# milestone1.net
KiCad netlist of a schematic drawn in Altium Designer
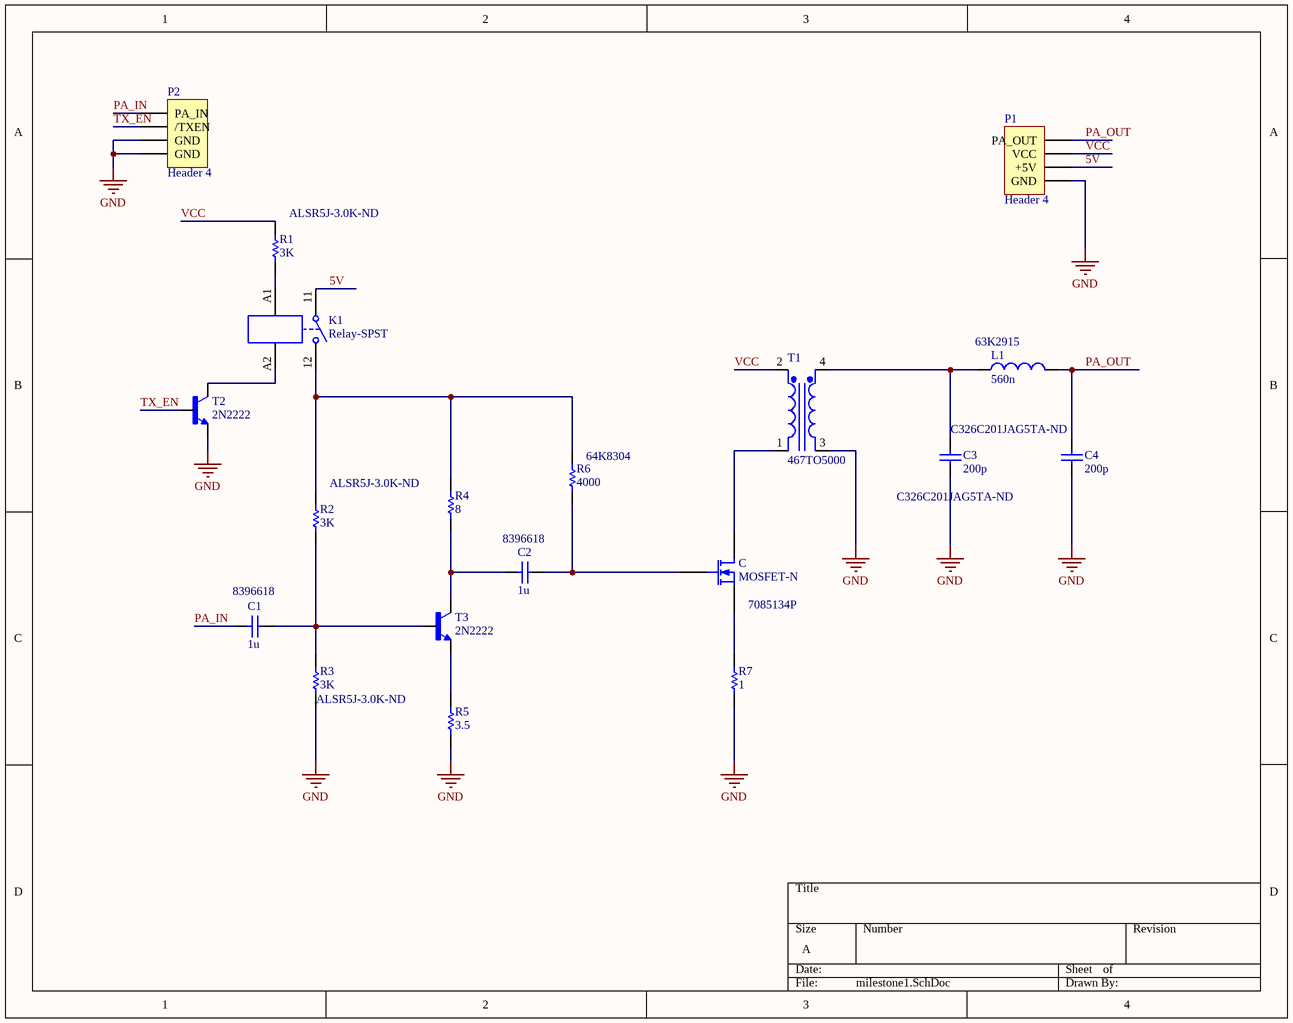
[diagram p0: milestone1.SchDoc]

(export (version "E")
  (design (tool "Eeschema 10.0.6"))
  (components
    (comp (ref "C")
      (value "MOSFET-N")
      (footprint "TO254P1067X483X3124-3P")
      (description "IRF510PBF N-channel MOSFET Transistor; 5.6 A; 100 V; 3-Pin TO-220AB")
      (fields
        (field (name "SUPPLIER PART NUMBER 1") "7085134P")
        (field (name "MANUFACTURER") "Vishay")
        (field (name "MANUFACTURER PART NUMBER") "IRF510PBF")
        (field (name "PUBLISHER") "Altium Limited")
      )
      (libsource (lib "Miscellaneous Devices") (part "MOSFET-N"))
    )
    (comp (ref "C1")
      (value "1u")
      (footprint "RAD-0.1")
      (description "Alum. Electrolytic Cap 1µF 50V 5mm Radial WCAP-ATG5 Series Lifetime 2000h +105°C")
      (fields
        (field (name "MANUFACTURER") "CDE Illinois Capacitor")
        (field (name "MANUFACTURER PART NUMBER") "109CKS016M")
        (field (name "SUPPLIER PART NUMBER 2") "8396618")
      )
      (libsource (lib "Simulation Generic Components") (part "Capacitor"))
    )
    (comp (ref "C2")
      (value "1u")
      (footprint "RAD-0.1")
      (description "Alum. Electrolytic Cap 1µF 50V 5mm Radial WCAP-ATG5 Series Lifetime 2000h +105°C")
      (fields
        (field (name "SUPPLIER PART NUMBER 1") "8396618")
        (field (name "MANUFACTURER") "Wurth Electronics")
        (field (name "MANUFACTURER PART NUMBER") "860020672005")
      )
      (libsource (lib "Simulation Generic Components") (part "Capacitor"))
    )
    (comp (ref "C3")
      (value "200p")
      (footprint "rad-0.1")
      (description "Capacitor Multi-layer Ceramic 200pF 5% 250V 2-Pin Through Hole Bulk")
      (fields
        (field (name "SUPPLIER PART NUMBER 1") "C326C201JAG5TA-ND")
        (field (name "MANUFACTURER") "KEMET")
        (field (name "MANUFACTURER PART NUMBER") "C326C201JAG5TA")
      )
      (libsource (lib "Simulation Generic Components") (part "Capacitor"))
    )
    (comp (ref "C4")
      (value "200p")
      (footprint "rad-0.1")
      (description "Capacitor Multi-layer Ceramic 200pF 5% 250V 2-Pin Through Hole Bulk")
      (fields
        (field (name "SUPPLIER PART NUMBER 1") "C326C201JAG5TA-ND")
        (field (name "MANUFACTURER") "KEMET")
        (field (name "MANUFACTURER PART NUMBER") "C326C201JAG5TA")
      )
      (libsource (lib "Simulation Generic Components") (part "Capacitor"))
    )
    (comp (ref "K1")
      (value "Relay-SPST")
      (footprint "Relay:PCBComponent_1")
      (description "Single-Pole Single-Throw Relay")
      (fields (field (name "PUBLISHER") "Altium Limited"))
      (libsource (lib "Miscellaneous Devices") (part "Relay-SPST"))
    )
    (comp (ref "L1")
      (value "560n")
      (footprint "AXIAL-0.4")
      (description "Inductor")
      (fields (field (name "SUPPLIER PART NUMBER 2") "63K2915"))
      (libsource (lib "Simulation Generic Components") (part "Inductor"))
    )
    (comp (ref "P1")
      (value "Header 4")
      (footprint "HDR1X4")
      (description "Header, 4-Pin")
      (fields (field (name "PUBLISHER") "Altium Limited"))
      (libsource (lib "") (part "Header 4_1"))
    )
    (comp (ref "P2")
      (value "Header 4")
      (footprint "HDR1X4")
      (description "Header, 4-Pin")
      (fields (field (name "PUBLISHER") "Altium Limited"))
      (libsource (lib "Miscellaneous Connectors") (part "Header 4"))
    )
    (comp (ref "R1")
      (value "3K")
      (footprint "AXIAL-0.4")
      (description "Res Wirewound 3K Ohm 5% 5W ±30ppm/°C Ceramic Hi Temp Sil AXL Thru-Hole Bulk")
      (fields
        (field (name "MANUFACTURER") "Vishay BCcomponents")
        (field (name "MANUFACTURER PART NUMBER") "MBA02040C3001FC100")
        (field (name "SUPPLIER PART NUMBER 2") "ALSR5J-3.0K-ND")
      )
      (libsource (lib "Simulation Generic Components") (part "Resistor"))
    )
    (comp (ref "R2")
      (value "3K")
      (footprint "AXIAL-0.4")
      (description "Res Wirewound 3K Ohm 5% 5W ±30ppm/°C Ceramic Hi Temp Sil AXL Thru-Hole Bulk")
      (fields
        (field (name "MANUFACTURER") "Vishay BCcomponents")
        (field (name "MANUFACTURER PART NUMBER") "MBA02040C3001FC100")
        (field (name "SUPPLIER PART NUMBER 2") "ALSR5J-3.0K-ND")
      )
      (libsource (lib "Simulation Generic Components") (part "Resistor"))
    )
    (comp (ref "R3")
      (value "3K")
      (footprint "AXIAL-0.4")
      (description "Res Wirewound 3K Ohm 5% 5W ±30ppm/°C Ceramic Hi Temp Sil AXL Thru-Hole Bulk")
      (fields
        (field (name "MANUFACTURER") "Vishay BCcomponents")
        (field (name "MANUFACTURER PART NUMBER") "MBA02040C3001FC100")
        (field (name "SUPPLIER PART NUMBER 3") "ALSR5J-3.0K-ND")
      )
      (libsource (lib "Simulation Generic Components") (part "Resistor"))
    )
    (comp (ref "R4")
      (value "8")
      (footprint "rad-0.1")
      (description "Resistor; Wirewound; Res 33 Ohms; Pwr-Rtg 5 W; Tol 1%; Axial; Silicone-Ceramic")
      (fields
        (field (name "MANUFACTURER") "Piher")
        (field (name "MANUFACTURER PART NUMBER") "N6S25T0C-504-3030")
      )
      (libsource (lib "Simulation Generic Components") (part "Resistor"))
    )
    (comp (ref "R5")
      (value "3.5")
      (footprint "rad-0.1")
      (description "Res Metal Film 1.5 Ohm 5% 3W ±300ppm/°C Conformal AXL Thru-Hole")
      (fields
        (field (name "MANUFACTURER") "Vishay Dale")
        (field (name "MANUFACTURER PART NUMBER") "RN70C2700BB14")
      )
      (libsource (lib "Simulation Generic Components") (part "Resistor"))
    )
    (comp (ref "R6")
      (value "4000")
      (footprint "AXIAL-0.4")
      (description "Resistor, Wirewound, Res 4 Kilohms, Pwr-Rtg 5 W, Tol 5%, Axial, Vitreous Enamel")
      (fields
        (field (name "MANUFACTURER") "Piher")
        (field (name "MANUFACTURER PART NUMBER") "N6S25T0C-504-3030")
        (field (name "SUPPLIER PART NUMBER 3") "64K8304")
      )
      (libsource (lib "Simulation Generic Components") (part "Resistor"))
    )
    (comp (ref "R7")
      (value "1")
      (footprint "AXIAL-0.4")
      (description "Res Wirewound 8K Ohm 5% 5W ±30ppm/°C Ceramic Hi Temp Sil AXL Thru-Hole Bulk")
      (fields
        (field (name "MANUFACTURER") "Vishay Dale")
        (field (name "MANUFACTURER PART NUMBER") "RN55C8001BB14")
      )
      (libsource (lib "Simulation Generic Components") (part "Resistor"))
    )
    (comp (ref "T1")
      (value "467TO5000")
      (footprint "TRANS")
      (description "Transformer (Ideal)")
      (fields (field (name "PUBLISHER") "Altium Limited"))
      (libsource (lib "Miscellaneous Devices") (part "Trans Ideal"))
    )
    (comp (ref "T2")
      (value "2N2222")
      (footprint "TO92-EBC-OVAL")
      (description "Bipolar (BJT) Transistor NPN 40V 800mA 300MHz 500mW Through Hole TO-18")
      (fields (field (name "MF") "ON Semiconductor"))
      (libsource (lib "2N2222 (2)") (part "2N2222"))
    )
    (comp (ref "T3")
      (value "2N2222")
      (footprint "TO92-EBC-OVAL")
      (description "Bipolar (BJT) Transistor NPN 40V 800mA 300MHz 500mW Through Hole TO-18")
      (fields (field (name "MF") "ON Semiconductor"))
      (libsource (lib "2N2222 (2)") (part "2N2222"))
    )
  )
  (nets
    (net (code "1") (name "/5V") (class "Default")
      (node (ref "K1") (pin "11") (pinfunction "SW1_11") (pintype "passive"))
      (node (ref "P1") (pin "2") (pinfunction "+5V_2") (pintype "passive"))
    )
    (net (code "2") (name "/PA_IN") (class "Default")
      (node (ref "C1") (pin "1") (pinfunction "1_1") (pintype "passive"))
      (node (ref "P2") (pin "1") (pinfunction "PA_IN_1") (pintype "passive"))
    )
    (net (code "3") (name "/PA_OUT") (class "Default")
      (node (ref "C4") (pin "2") (pinfunction "2_2") (pintype "passive"))
      (node (ref "L1") (pin "2") (pinfunction "2_2") (pintype "passive"))
      (node (ref "P1") (pin "4") (pinfunction "PA_OUT_4") (pintype "passive"))
    )
    (net (code "4") (name "/TX_EN") (class "Default")
      (node (ref "P2") (pin "2") (pinfunction "/TXEN_2") (pintype "passive"))
      (node (ref "T2") (pin "B") (pinfunction "B_B") (pintype "passive"))
    )
    (net (code "5") (name "/VCC") (class "Default")
      (node (ref "P1") (pin "3") (pinfunction "VCC_3") (pintype "passive"))
      (node (ref "R1") (pin "2") (pinfunction "2_2") (pintype "passive"))
      (node (ref "T1") (pin "2") (pinfunction "Pri+_2") (pintype "passive"))
    )
    (net (code "6") (name "GND") (class "Default")
      (node (ref "C3") (pin "1") (pinfunction "1_1") (pintype "passive"))
      (node (ref "C4") (pin "1") (pinfunction "1_1") (pintype "passive"))
      (node (ref "P1") (pin "1") (pinfunction "GND_1") (pintype "passive"))
      (node (ref "P2") (pin "3") (pinfunction "GND_3") (pintype "passive"))
      (node (ref "P2") (pin "4") (pinfunction "GND_4") (pintype "passive"))
      (node (ref "R3") (pin "1") (pinfunction "1_1") (pintype "passive"))
      (node (ref "R5") (pin "1") (pinfunction "1_1") (pintype "passive"))
      (node (ref "R7") (pin "1") (pinfunction "1_1") (pintype "passive"))
      (node (ref "T1") (pin "3") (pinfunction "Sec-_3") (pintype "passive"))
      (node (ref "T2") (pin "E") (pinfunction "E_E") (pintype "passive"))
    )
    (net (code "7") (name "Net-(C-D)") (class "Default")
      (node (ref "C") (pin "1") (pinfunction "D_1") (pintype "passive"))
      (node (ref "T1") (pin "1") (pinfunction "Pri-_1") (pintype "passive"))
    )
    (net (code "8") (name "Net-(C-G)") (class "Default")
      (node (ref "C") (pin "2") (pinfunction "G_2") (pintype "passive"))
      (node (ref "C2") (pin "2") (pinfunction "2_2") (pintype "passive"))
      (node (ref "R6") (pin "1") (pinfunction "1_1") (pintype "passive"))
    )
    (net (code "9") (name "Net-(C-S)") (class "Default")
      (node (ref "C") (pin "3") (pinfunction "S_3") (pintype "passive"))
      (node (ref "R7") (pin "2") (pinfunction "2_2") (pintype "passive"))
    )
    (net (code "10") (name "Net-(C1-Pad2)") (class "Default")
      (node (ref "C1") (pin "2") (pinfunction "2_2") (pintype "passive"))
      (node (ref "R2") (pin "1") (pinfunction "1_1") (pintype "passive"))
      (node (ref "R3") (pin "2") (pinfunction "2_2") (pintype "passive"))
      (node (ref "T3") (pin "B") (pinfunction "B_B") (pintype "passive"))
    )
    (net (code "11") (name "Net-(C2-Pad1)") (class "Default")
      (node (ref "C2") (pin "1") (pinfunction "1_1") (pintype "passive"))
      (node (ref "R4") (pin "1") (pinfunction "1_1") (pintype "passive"))
      (node (ref "T3") (pin "C") (pinfunction "C_C") (pintype "passive"))
    )
    (net (code "12") (name "Net-(K1-Coil1)") (class "Default")
      (node (ref "K1") (pin "A1") (pinfunction "Coil1_A1") (pintype "passive"))
      (node (ref "R1") (pin "1") (pinfunction "1_1") (pintype "passive"))
    )
    (net (code "13") (name "Net-(K1-Coil2)") (class "Default")
      (node (ref "K1") (pin "A2") (pinfunction "Coil2_A2") (pintype "passive"))
      (node (ref "T2") (pin "C") (pinfunction "C_C") (pintype "passive"))
    )
    (net (code "14") (name "Net-(K1-SW2)") (class "Default")
      (node (ref "K1") (pin "12") (pinfunction "SW2_12") (pintype "passive"))
      (node (ref "R2") (pin "2") (pinfunction "2_2") (pintype "passive"))
      (node (ref "R4") (pin "2") (pinfunction "2_2") (pintype "passive"))
      (node (ref "R6") (pin "2") (pinfunction "2_2") (pintype "passive"))
    )
    (net (code "15") (name "Net-(R5-Pad2)") (class "Default")
      (node (ref "R5") (pin "2") (pinfunction "2_2") (pintype "passive"))
      (node (ref "T3") (pin "E") (pinfunction "E_E") (pintype "passive"))
    )
    (net (code "16") (name "Net-(T1-Sec+)") (class "Default")
      (node (ref "C3") (pin "2") (pinfunction "2_2") (pintype "passive"))
      (node (ref "L1") (pin "1") (pinfunction "1_1") (pintype "passive"))
      (node (ref "T1") (pin "4") (pinfunction "Sec+_4") (pintype "passive"))
    )
  )
)
